# mcu.net
KiCad netlist of a schematic drawn in Altium Designer
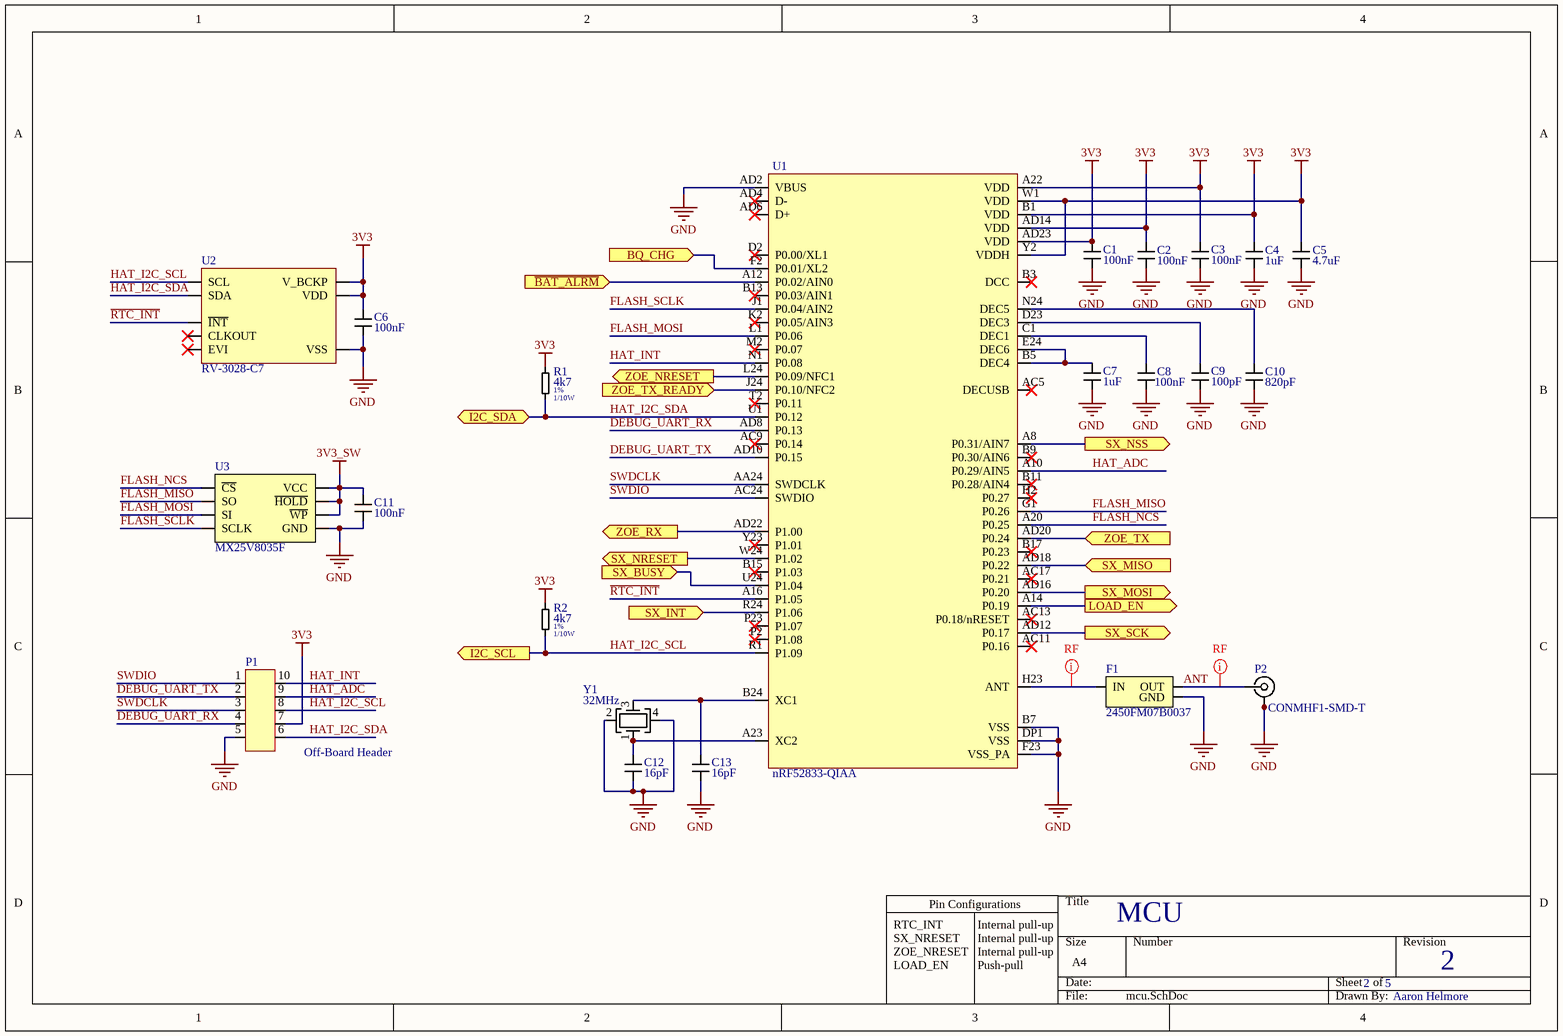
[diagram p0: mcu.SchDoc]

(export (version "E")
  (design (tool "Eeschema 10.0.6"))
  (components
    (comp (ref "C1")
      (value "100nF")
      (footprint "CAP_0402")
      (fields (field (name "VOLTAGE") "25V"))
      (libsource (lib "thesis_schem_lib") (part "Capacitor"))
    )
    (comp (ref "C2")
      (value "100nF")
      (footprint "CAP_0402")
      (fields (field (name "VOLTAGE") "25V"))
      (libsource (lib "thesis_schem_lib") (part "Capacitor"))
    )
    (comp (ref "C3")
      (value "100nF")
      (footprint "CAP_0402")
      (fields (field (name "VOLTAGE") "25V"))
      (libsource (lib "thesis_schem_lib") (part "Capacitor"))
    )
    (comp (ref "C4")
      (value "1uF")
      (footprint "CAP_0402")
      (fields (field (name "VOLTAGE") "25V"))
      (libsource (lib "thesis_schem_lib") (part "Capacitor"))
    )
    (comp (ref "C5")
      (value "4.7uF")
      (footprint "CAP_0603")
      (fields (field (name "VOLTAGE") "6.3V"))
      (libsource (lib "thesis_schem_lib") (part "Capacitor"))
    )
    (comp (ref "C6")
      (value "100nF")
      (footprint "CAP_0402")
      (fields (field (name "VOLTAGE") "25V"))
      (libsource (lib "thesis_schem_lib") (part "Capacitor"))
    )
    (comp (ref "C7")
      (value "1uF")
      (footprint "CAP_0402")
      (fields (field (name "VOLTAGE") "25V"))
      (libsource (lib "thesis_schem_lib") (part "Capacitor"))
    )
    (comp (ref "C8")
      (value "100nF")
      (footprint "CAP_0402")
      (fields (field (name "VOLTAGE") "25V"))
      (libsource (lib "thesis_schem_lib") (part "Capacitor"))
    )
    (comp (ref "C9")
      (value "100pF")
      (footprint "CAP_0402")
      (fields (field (name "VOLTAGE") "50V"))
      (libsource (lib "thesis_schem_lib") (part "Capacitor"))
    )
    (comp (ref "C10")
      (value "820pF")
      (footprint "CAP_0402")
      (fields (field (name "VOLTAGE") "50V"))
      (libsource (lib "thesis_schem_lib") (part "Capacitor"))
    )
    (comp (ref "C11")
      (value "100nF")
      (footprint "CAP_0402")
      (fields (field (name "VOLTAGE") "25V"))
      (libsource (lib "thesis_schem_lib") (part "Capacitor"))
    )
    (comp (ref "C12")
      (value "16pF")
      (footprint "CAP_0402")
      (fields (field (name "VOLTAGE") "50V"))
      (libsource (lib "thesis_schem_lib") (part "Capacitor"))
    )
    (comp (ref "C13")
      (value "16pF")
      (footprint "CAP_0402")
      (fields (field (name "VOLTAGE") "50V"))
      (libsource (lib "thesis_schem_lib") (part "Capacitor"))
    )
    (comp (ref "F1")
      (value "2450FM07B0037")
      (footprint "2450FM07B0037")
      (description "Miniature 2.4GHz impedance matched low pass filter optimized for nRF52xxx")
      (libsource (lib "thesis_schem_lib") (part "2450FM07B0037"))
    )
    (comp (ref "P1")
      (value "Off-Board Header")
      (footprint "1_27-5x2-MALE-HEADER")
      (description "1.27mm pitch 5x2 pin male connector")
      (libsource (lib "thesis_schem_lib") (part "CONN_1-27_5x2"))
    )
    (comp (ref "P2")
      (value "CONMHF1-SMD-T")
      (footprint "CONMHF1-SMD-T")
      (libsource (lib "thesis_schem_lib") (part "CONMHF1-SMD-T"))
    )
    (comp (ref "R1")
      (value "4k7")
      (footprint "RES_0402")
      (fields (field (name "TOLERANCE") "1%") (field (name "WATTAGE") "1/10W"))
      (libsource (lib "thesis_schem_lib") (part "R_Small"))
    )
    (comp (ref "R2")
      (value "4k7")
      (footprint "RES_0402")
      (fields (field (name "TOLERANCE") "1%") (field (name "WATTAGE") "1/10W"))
      (libsource (lib "thesis_schem_lib") (part "R_Small"))
    )
    (comp (ref "U1")
      (value "nRF52833-QIAA")
      (footprint "nRF52833-QIAA")
      (description "BLE 5.1, Cortex M-4 SoC")
      (libsource (lib "thesis_schem_lib") (part "nRF52833-QIAA"))
    )
    (comp (ref "U2")
      (value "RV-3028-C7")
      (footprint "RV-3028-C7")
      (description "Extreme Low Power RTC Module")
      (libsource (lib "thesis_schem_lib") (part "RV-3028-C7"))
    )
    (comp (ref "U3")
      (value "MX25V8035F")
      (footprint "MX25V8035F")
      (libsource (lib "thesis_schem_lib") (part "MX25V8035F"))
    )
    (comp (ref "Y1")
      (value "32MHz")
      (footprint "4-SMD")
      (libsource (lib "thesis_schem_lib") (part "Crystal_2_2"))
    )
  )
  (nets
    (net (code "1") (name "/ANT") (class "Default")
      (node (ref "F1") (pin "3") (pinfunction "OUT_3") (pintype "passive"))
      (node (ref "P2") (pin "1") (pinfunction "VCC_1") (pintype "passive"))
    )
    (net (code "2") (name "/BQ_CHG") (class "Default")
      (node (ref "U1") (pin "F2") (pinfunction "P0.01/XL2_F2") (pintype "passive"))
    )
    (net (code "3") (name "/DEBUG_UART_RX") (class "Default")
      (node (ref "P1") (pin "4") (pintype "passive"))
      (node (ref "U1") (pin "AD8") (pinfunction "P0.13_AD8") (pintype "passive"))
    )
    (net (code "4") (name "/DEBUG_UART_TX") (class "Default")
      (node (ref "P1") (pin "2") (pintype "passive"))
      (node (ref "U1") (pin "AD10") (pinfunction "P0.15_AD10") (pintype "passive"))
    )
    (net (code "5") (name "/FLASH_MISO") (class "Default")
      (node (ref "U1") (pin "G1") (pinfunction "P0.26_G1") (pintype "passive"))
      (node (ref "U3") (pin "2") (pinfunction "SO_2") (pintype "passive"))
    )
    (net (code "6") (name "/FLASH_MOSI") (class "Default")
      (node (ref "U1") (pin "L1") (pinfunction "P0.06_L1") (pintype "passive"))
      (node (ref "U3") (pin "5") (pinfunction "SI_5") (pintype "passive"))
    )
    (net (code "7") (name "/FLASH_NCS") (class "Default")
      (node (ref "U1") (pin "A20") (pinfunction "P0.25_A20") (pintype "passive"))
      (node (ref "U3") (pin "1") (pinfunction "~{CS}_1") (pintype "passive"))
    )
    (net (code "8") (name "/FLASH_SCLK") (class "Default")
      (node (ref "U1") (pin "J1") (pinfunction "P0.04/AIN2_J1") (pintype "passive"))
      (node (ref "U3") (pin "6") (pinfunction "SCLK_6") (pintype "passive"))
    )
    (net (code "9") (name "/HAT_ADC") (class "Default")
      (node (ref "P1") (pin "9") (pintype "passive"))
      (node (ref "U1") (pin "A10") (pinfunction "P0.29/AIN5_A10") (pintype "passive"))
    )
    (net (code "10") (name "/HAT_I2C_SCL") (class "Default")
      (node (ref "P1") (pin "8") (pintype "passive"))
      (node (ref "R2") (pin "2") (pinfunction "2_2") (pintype "passive"))
      (node (ref "U1") (pin "R1") (pinfunction "P1.09_R1") (pintype "passive"))
      (node (ref "U2") (pin "3") (pinfunction "SCL_3") (pintype "passive"))
    )
    (net (code "11") (name "/HAT_I2C_SDA") (class "Default")
      (node (ref "P1") (pin "6") (pintype "passive"))
      (node (ref "R1") (pin "2") (pinfunction "2_2") (pintype "passive"))
      (node (ref "U1") (pin "U1") (pinfunction "P0.12_U1") (pintype "passive"))
      (node (ref "U2") (pin "4") (pinfunction "SDA_4") (pintype "passive"))
    )
    (net (code "12") (name "/HAT_INT") (class "Default")
      (node (ref "P1") (pin "10") (pintype "passive"))
      (node (ref "U1") (pin "N1") (pinfunction "P0.08_N1") (pintype "passive"))
    )
    (net (code "13") (name "/LOAD_EN") (class "Default")
      (node (ref "U1") (pin "A14") (pinfunction "P0.19_A14") (pintype "passive"))
    )
    (net (code "14") (name "/SWDCLK") (class "Default")
      (node (ref "P1") (pin "3") (pintype "passive"))
      (node (ref "U1") (pin "AA24") (pinfunction "SWDCLK_AA24") (pintype "passive"))
    )
    (net (code "15") (name "/SWDIO") (class "Default")
      (node (ref "P1") (pin "1") (pintype "passive"))
      (node (ref "U1") (pin "AC24") (pinfunction "SWDIO_AC24") (pintype "passive"))
    )
    (net (code "16") (name "/SX_BUSY") (class "Default")
      (node (ref "U1") (pin "U24") (pinfunction "P1.04_U24") (pintype "passive"))
    )
    (net (code "17") (name "/SX_INT") (class "Default")
      (node (ref "U1") (pin "R24") (pinfunction "P1.06_R24") (pintype "passive"))
    )
    (net (code "18") (name "/SX_MISO") (class "Default")
      (node (ref "U1") (pin "AD18") (pinfunction "P0.22_AD18") (pintype "passive"))
    )
    (net (code "19") (name "/SX_MOSI") (class "Default")
      (node (ref "U1") (pin "AD16") (pinfunction "P0.20_AD16") (pintype "passive"))
    )
    (net (code "20") (name "/SX_NRESET") (class "Default")
      (node (ref "U1") (pin "W24") (pinfunction "P1.02_W24") (pintype "passive"))
    )
    (net (code "21") (name "/SX_NSS") (class "Default")
      (node (ref "U1") (pin "A8") (pinfunction "P0.31/AIN7_A8") (pintype "passive"))
    )
    (net (code "22") (name "/SX_SCK") (class "Default")
      (node (ref "U1") (pin "AD12") (pinfunction "P0.17_AD12") (pintype "passive"))
    )
    (net (code "23") (name "/ZOE_NRESET") (class "Default")
      (node (ref "U1") (pin "L24") (pinfunction "P0.09/NFC1_L24") (pintype "passive"))
    )
    (net (code "24") (name "/ZOE_RX") (class "Default")
      (node (ref "U1") (pin "AD22") (pinfunction "P1.00_AD22") (pintype "passive"))
    )
    (net (code "25") (name "/ZOE_TX") (class "Default")
      (node (ref "U1") (pin "AD20") (pinfunction "P0.24_AD20") (pintype "passive"))
    )
    (net (code "26") (name "/ZOE_TX_READY") (class "Default")
      (node (ref "U1") (pin "J24") (pinfunction "P0.10/NFC2_J24") (pintype "passive"))
    )
    (net (code "27") (name "/~{BAT_ALRM}") (class "Default")
      (node (ref "U1") (pin "A12") (pinfunction "P0.02/AIN0_A12") (pintype "passive"))
    )
    (net (code "28") (name "/~{RTC_INT}") (class "Default")
      (node (ref "U1") (pin "A16") (pinfunction "P1.05_A16") (pintype "passive"))
      (node (ref "U2") (pin "2") (pinfunction "~{INT}_2") (pintype "passive"))
    )
    (net (code "29") (name "3V3") (class "Default")
      (node (ref "C1") (pin "2") (pinfunction "J11_2") (pintype "passive"))
      (node (ref "C2") (pin "2") (pinfunction "J11_2") (pintype "passive"))
      (node (ref "C3") (pin "2") (pinfunction "J11_2") (pintype "passive"))
      (node (ref "C4") (pin "2") (pinfunction "J11_2") (pintype "passive"))
      (node (ref "C5") (pin "2") (pinfunction "J11_2") (pintype "passive"))
      (node (ref "C6") (pin "2") (pinfunction "J11_2") (pintype "passive"))
      (node (ref "P1") (pin "7") (pintype "passive"))
      (node (ref "R1") (pin "1") (pinfunction "1_1") (pintype "passive"))
      (node (ref "R2") (pin "1") (pinfunction "1_1") (pintype "passive"))
      (node (ref "U1") (pin "A22") (pinfunction "VDD_A22") (pintype "passive"))
      (node (ref "U1") (pin "AD14") (pinfunction "VDD_AD14") (pintype "passive"))
      (node (ref "U1") (pin "AD23") (pinfunction "VDD_AD23") (pintype "passive"))
      (node (ref "U1") (pin "B1") (pinfunction "VDD_B1") (pintype "passive"))
      (node (ref "U1") (pin "W1") (pinfunction "VDD_W1") (pintype "passive"))
      (node (ref "U1") (pin "Y2") (pinfunction "VDDH_Y2") (pintype "passive"))
      (node (ref "U2") (pin "6") (pinfunction "V_BCKP_6") (pintype "passive"))
      (node (ref "U2") (pin "7") (pinfunction "VDD_7") (pintype "passive"))
    )
    (net (code "30") (name "3V3_SW") (class "Default")
      (node (ref "C11") (pin "2") (pinfunction "J11_2") (pintype "passive"))
      (node (ref "U3") (pin "3") (pinfunction "~{WP}_3") (pintype "passive"))
      (node (ref "U3") (pin "7") (pinfunction "~{HOLD}_7") (pintype "passive"))
      (node (ref "U3") (pin "8") (pinfunction "VCC_8") (pintype "passive"))
    )
    (net (code "31") (name "GND") (class "Default")
      (node (ref "C1") (pin "1") (pinfunction "J12_1") (pintype "passive"))
      (node (ref "C10") (pin "1") (pinfunction "J12_1") (pintype "passive"))
      (node (ref "C11") (pin "1") (pinfunction "J12_1") (pintype "passive"))
      (node (ref "C12") (pin "1") (pinfunction "J12_1") (pintype "passive"))
      (node (ref "C13") (pin "1") (pinfunction "J12_1") (pintype "passive"))
      (node (ref "C2") (pin "1") (pinfunction "J12_1") (pintype "passive"))
      (node (ref "C3") (pin "1") (pinfunction "J12_1") (pintype "passive"))
      (node (ref "C4") (pin "1") (pinfunction "J12_1") (pintype "passive"))
      (node (ref "C5") (pin "1") (pinfunction "J12_1") (pintype "passive"))
      (node (ref "C6") (pin "1") (pinfunction "J12_1") (pintype "passive"))
      (node (ref "C7") (pin "1") (pinfunction "J12_1") (pintype "passive"))
      (node (ref "C8") (pin "1") (pinfunction "J12_1") (pintype "passive"))
      (node (ref "C9") (pin "1") (pinfunction "J12_1") (pintype "passive"))
      (node (ref "F1") (pin "2") (pinfunction "GND_2") (pintype "passive"))
      (node (ref "P1") (pin "5") (pintype "passive"))
      (node (ref "P2") (pin "2") (pinfunction "VCC_2") (pintype "passive"))
      (node (ref "P2") (pin "3") (pinfunction "VCC_3") (pintype "passive"))
      (node (ref "P2") (pin "4") (pinfunction "VCC_4") (pintype "passive"))
      (node (ref "U1") (pin "AD2") (pinfunction "VBUS_AD2") (pintype "passive"))
      (node (ref "U1") (pin "B7") (pinfunction "VSS_B7") (pintype "passive"))
      (node (ref "U1") (pin "DP1") (pinfunction "VSS_DP1") (pintype "passive"))
      (node (ref "U1") (pin "F23") (pinfunction "VSS_PA_F23") (pintype "passive"))
      (node (ref "U2") (pin "5") (pinfunction "VSS_5") (pintype "passive"))
      (node (ref "U3") (pin "4") (pinfunction "GND_4") (pintype "passive"))
      (node (ref "Y1") (pin "2") (pinfunction "2_2") (pintype "passive"))
      (node (ref "Y1") (pin "4") (pinfunction "4_4") (pintype "passive"))
    )
    (net (code "32") (name "Net-(C7-J11)") (class "Default")
      (node (ref "C7") (pin "2") (pinfunction "J11_2") (pintype "passive"))
      (node (ref "U1") (pin "B5") (pinfunction "DEC4_B5") (pintype "passive"))
      (node (ref "U1") (pin "E24") (pinfunction "DEC6_E24") (pintype "passive"))
    )
    (net (code "33") (name "Net-(C8-J11)") (class "Default")
      (node (ref "C8") (pin "2") (pinfunction "J11_2") (pintype "passive"))
      (node (ref "U1") (pin "C1") (pinfunction "DEC1_C1") (pintype "passive"))
    )
    (net (code "34") (name "Net-(C9-J11)") (class "Default")
      (node (ref "C9") (pin "2") (pinfunction "J11_2") (pintype "passive"))
      (node (ref "U1") (pin "D23") (pinfunction "DEC3_D23") (pintype "passive"))
    )
    (net (code "35") (name "Net-(C10-J11)") (class "Default")
      (node (ref "C10") (pin "2") (pinfunction "J11_2") (pintype "passive"))
      (node (ref "U1") (pin "N24") (pinfunction "DEC5_N24") (pintype "passive"))
    )
    (net (code "36") (name "Net-(C12-J11)") (class "Default")
      (node (ref "C12") (pin "2") (pinfunction "J11_2") (pintype "passive"))
      (node (ref "U1") (pin "A23") (pinfunction "XC2_A23") (pintype "passive"))
      (node (ref "Y1") (pin "1") (pinfunction "1_1") (pintype "passive"))
    )
    (net (code "37") (name "Net-(C13-J11)") (class "Default")
      (node (ref "C13") (pin "2") (pinfunction "J11_2") (pintype "passive"))
      (node (ref "U1") (pin "B24") (pinfunction "XC1_B24") (pintype "passive"))
      (node (ref "Y1") (pin "3") (pinfunction "3_3") (pintype "passive"))
    )
    (net (code "38") (name "Net-(F1-IN)") (class "Default")
      (node (ref "F1") (pin "1") (pinfunction "IN_1") (pintype "passive"))
      (node (ref "U1") (pin "H23") (pinfunction "ANT_H23") (pintype "passive"))
    )
    (net (code "39") (name "unconnected-(U1-D+-PadAD6)") (class "Default")
      (node (ref "U1") (pin "AD6") (pinfunction "D+_AD6") (pintype "passive+no_connect"))
    )
    (net (code "40") (name "unconnected-(U1-D--PadAD4)") (class "Default")
      (node (ref "U1") (pin "AD4") (pinfunction "D-_AD4") (pintype "passive+no_connect"))
    )
    (net (code "41") (name "unconnected-(U1-DCC-PadB3)") (class "Default")
      (node (ref "U1") (pin "B3") (pinfunction "DCC_B3") (pintype "passive+no_connect"))
    )
    (net (code "42") (name "unconnected-(U1-DECUSB-PadAC5)") (class "Default")
      (node (ref "U1") (pin "AC5") (pinfunction "DECUSB_AC5") (pintype "passive+no_connect"))
    )
    (net (code "43") (name "unconnected-(U1-P0.00{slash}XL1-PadD2)") (class "Default")
      (node (ref "U1") (pin "D2") (pinfunction "P0.00/XL1_D2") (pintype "passive+no_connect"))
    )
    (net (code "44") (name "unconnected-(U1-P0.03{slash}AIN1-PadB13)") (class "Default")
      (node (ref "U1") (pin "B13") (pinfunction "P0.03/AIN1_B13") (pintype "passive+no_connect"))
    )
    (net (code "45") (name "unconnected-(U1-P0.05{slash}AIN3-PadK2)") (class "Default")
      (node (ref "U1") (pin "K2") (pinfunction "P0.05/AIN3_K2") (pintype "passive+no_connect"))
    )
    (net (code "46") (name "unconnected-(U1-P0.07-PadM2)") (class "Default")
      (node (ref "U1") (pin "M2") (pinfunction "P0.07_M2") (pintype "passive+no_connect"))
    )
    (net (code "47") (name "unconnected-(U1-P0.11-PadT2)") (class "Default")
      (node (ref "U1") (pin "T2") (pinfunction "P0.11_T2") (pintype "passive+no_connect"))
    )
    (net (code "48") (name "unconnected-(U1-P0.14-PadAC9)") (class "Default")
      (node (ref "U1") (pin "AC9") (pinfunction "P0.14_AC9") (pintype "passive+no_connect"))
    )
    (net (code "49") (name "unconnected-(U1-P0.16-PadAC11)") (class "Default")
      (node (ref "U1") (pin "AC11") (pinfunction "P0.16_AC11") (pintype "passive+no_connect"))
    )
    (net (code "50") (name "unconnected-(U1-P0.18{slash}nRESET-PadAC13)") (class "Default")
      (node (ref "U1") (pin "AC13") (pinfunction "P0.18/nRESET_AC13") (pintype "passive+no_connect"))
    )
    (net (code "51") (name "unconnected-(U1-P0.21-PadAC17)") (class "Default")
      (node (ref "U1") (pin "AC17") (pinfunction "P0.21_AC17") (pintype "passive+no_connect"))
    )
    (net (code "52") (name "unconnected-(U1-P0.23-PadB17)") (class "Default")
      (node (ref "U1") (pin "B17") (pinfunction "P0.23_B17") (pintype "passive+no_connect"))
    )
    (net (code "53") (name "unconnected-(U1-P0.27-PadH2)") (class "Default")
      (node (ref "U1") (pin "H2") (pinfunction "P0.27_H2") (pintype "passive+no_connect"))
    )
    (net (code "54") (name "unconnected-(U1-P0.28{slash}AIN4-PadB11)") (class "Default")
      (node (ref "U1") (pin "B11") (pinfunction "P0.28/AIN4_B11") (pintype "passive+no_connect"))
    )
    (net (code "55") (name "unconnected-(U1-P0.30{slash}AIN6-PadB9)") (class "Default")
      (node (ref "U1") (pin "B9") (pinfunction "P0.30/AIN6_B9") (pintype "passive+no_connect"))
    )
    (net (code "56") (name "unconnected-(U1-P1.01-PadY23)") (class "Default")
      (node (ref "U1") (pin "Y23") (pinfunction "P1.01_Y23") (pintype "passive+no_connect"))
    )
    (net (code "57") (name "unconnected-(U1-P1.03-PadB15)") (class "Default")
      (node (ref "U1") (pin "B15") (pinfunction "P1.03_B15") (pintype "passive+no_connect"))
    )
    (net (code "58") (name "unconnected-(U1-P1.07-PadP23)") (class "Default")
      (node (ref "U1") (pin "P23") (pinfunction "P1.07_P23") (pintype "passive+no_connect"))
    )
    (net (code "59") (name "unconnected-(U1-P1.08-PadP2)") (class "Default")
      (node (ref "U1") (pin "P2") (pinfunction "P1.08_P2") (pintype "passive+no_connect"))
    )
    (net (code "60") (name "unconnected-(U2-CLKOUT-Pad1)") (class "Default")
      (node (ref "U2") (pin "1") (pinfunction "CLKOUT_1") (pintype "passive+no_connect"))
    )
    (net (code "61") (name "unconnected-(U2-EVI-Pad8)") (class "Default")
      (node (ref "U2") (pin "8") (pinfunction "EVI_8") (pintype "passive+no_connect"))
    )
  )
)
